# CCP_MCU.net
KiCad netlist of a schematic drawn in Altium Designer
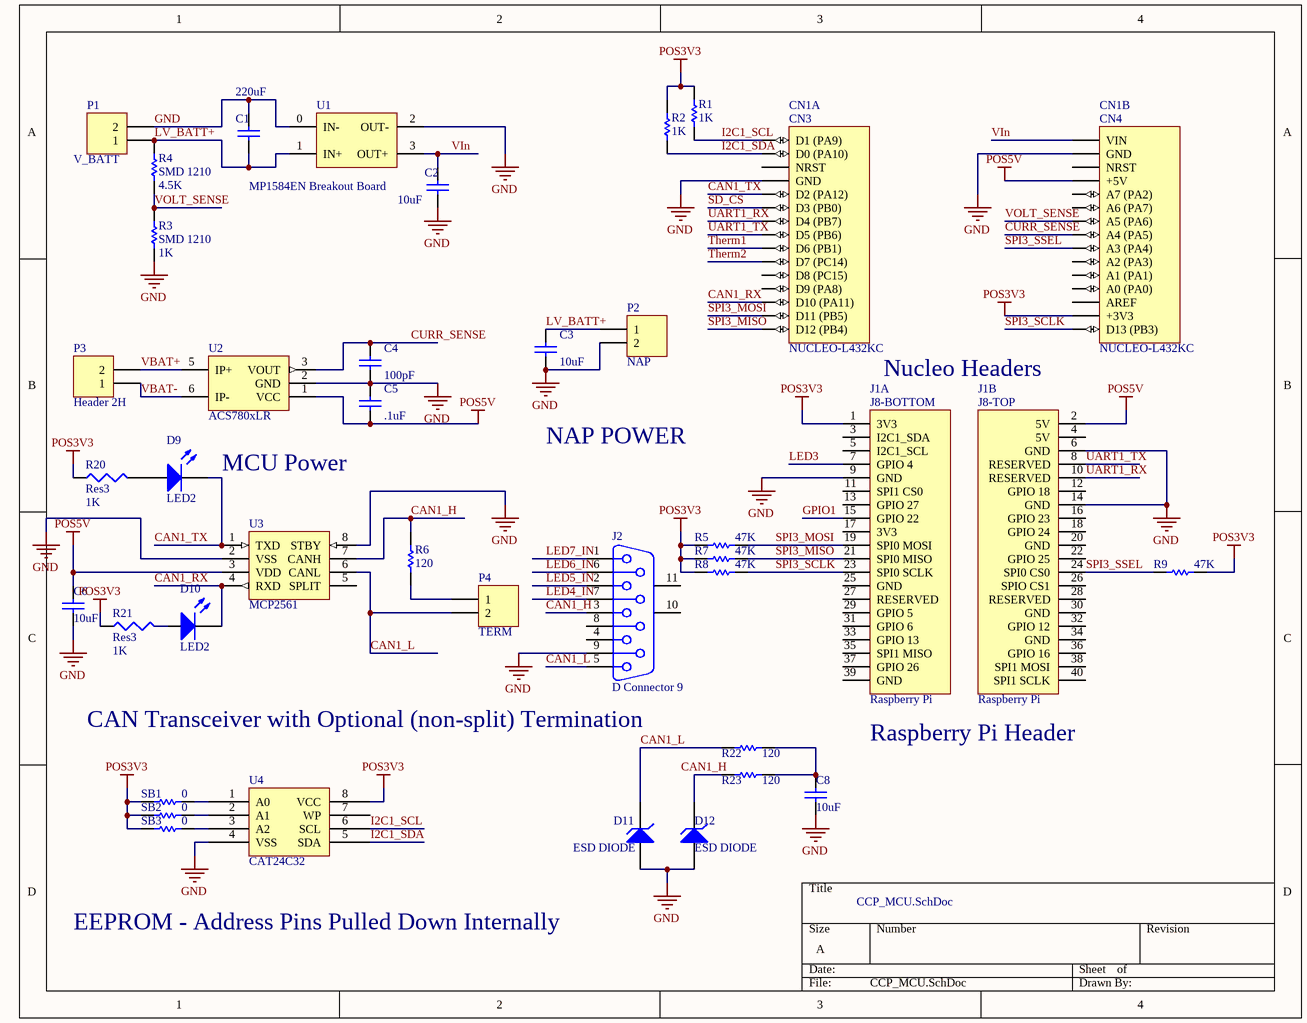
[diagram p0: CCP_MCU.SchDoc]

(export (version "E")
  (design (tool "Eeschema 10.0.6"))
  (components
    (comp (ref "C1")
      (value "220uF")
      (footprint "CAPR5-4X5")
      (description "Capacitor")
      (fields (field (name "Comment") "Cap") (field (name "PUBLISHER") "Altium Limited"))
      (libsource (lib "Miscellaneous Devices") (part "Cap"))
    )
    (comp (ref "C2")
      (value "10uF")
      (footprint "C1206")
      (description "Capacitor")
      (fields (field (name "Comment") "Cap") (field (name "PUBLISHER") "Altium Limited"))
      (libsource (lib "Miscellaneous Devices") (part "Cap"))
    )
    (comp (ref "C3")
      (value "10uF")
      (footprint "C1206")
      (description "Capacitor")
      (fields (field (name "Comment") "Cap") (field (name "PUBLISHER") "Altium Limited"))
      (libsource (lib "Miscellaneous Devices") (part "Cap"))
    )
    (comp (ref "C4")
      (value "100pF")
      (footprint "1608[0603]")
      (description "Capacitor (Semiconductor SIM Model)")
      (fields (field (name "Comment") "Cap Semi") (field (name "PUBLISHER") "Altium Limited"))
      (libsource (lib "Miscellaneous Devices") (part "Cap Semi"))
    )
    (comp (ref "C5")
      (value ".1uF")
      (footprint "C1206")
      (description "Capacitor (Semiconductor SIM Model)")
      (fields (field (name "Comment") "Cap Semi") (field (name "PUBLISHER") "Altium Limited"))
      (libsource (lib "Miscellaneous Devices") (part "Cap Semi"))
    )
    (comp (ref "C6")
      (value "10uF")
      (footprint "C1206")
      (description "Capacitor")
      (fields (field (name "Comment") "Cap") (field (name "PUBLISHER") "Altium Limited"))
      (libsource (lib "Miscellaneous Devices") (part "Cap"))
    )
    (comp (ref "C8")
      (value "10uF")
      (footprint "C1206")
      (description "Capacitor")
      (fields (field (name "Comment") "Cap") (field (name "PUBLISHER") "Altium Limited"))
      (libsource (lib "Miscellaneous Devices") (part "Cap"))
    )
    (comp (ref "CN1")
      (value "NUCLEO-L432KC")
      (footprint "NUCLEO-32")
      (description "STM32L432KC Development Board")
      (libsource (lib "ic") (part "NUCLEO-L432KC"))
    )
    (comp (ref "D9")
      (value "LED2")
      (footprint "3.2X1.6X1.1")
      (description "Typical RED, GREEN, YELLOW, AMBER GaAs LED")
      (fields (field (name "PUBLISHER") "Altium Limited"))
      (libsource (lib "Miscellaneous Devices") (part "LED2"))
    )
    (comp (ref "D10")
      (value "LED2")
      (footprint "3.2X1.6X1.1")
      (description "Typical RED, GREEN, YELLOW, AMBER GaAs LED")
      (fields (field (name "PUBLISHER") "Altium Limited"))
      (libsource (lib "Miscellaneous Devices") (part "LED2"))
    )
    (comp (ref "D11")
      (value "ESD DIODE")
      (footprint "6-0805_M")
      (description "Zener Diode")
      (fields (field (name "PUBLISHER") "Altium Limited"))
      (libsource (lib "Miscellaneous Devices") (part "D Zener"))
    )
    (comp (ref "D12")
      (value "ESD DIODE")
      (footprint "6-0805_M")
      (description "Zener Diode")
      (fields (field (name "PUBLISHER") "Altium Limited"))
      (libsource (lib "Miscellaneous Devices") (part "D Zener"))
    )
    (comp (ref "J1")
      (value "Raspberry Pi")
      (footprint "Raspberry Pi - CCP Outline")
      (description "2x20 Header")
      (libsource (lib "connector") (part "Raspberry Pi"))
    )
    (comp (ref "J2")
      (value "D Connector 9")
      (footprint "DSUB1.385-2H9")
      (description "Receptacle Assembly, 9 Position, Right Angle")
      (fields (field (name "PUBLISHER") "Altium Limited"))
      (libsource (lib "Miscellaneous Connectors") (part "D Connector 9"))
    )
    (comp (ref "P1")
      (value "V_BATT")
      (footprint "2POS TERM BLOCK")
      (description "Header, 2-Pin")
      (fields (field (name "PUBLISHER") "Altium Limited"))
      (libsource (lib "Miscellaneous Connectors") (part "Header 2"))
    )
    (comp (ref "P2")
      (value "NAP")
      (footprint "2POS TERM BLOCK")
      (description "Header, 2-Pin")
      (fields (field (name "PUBLISHER") "Altium Limited"))
      (libsource (lib "") (part "Header 2_1"))
    )
    (comp (ref "P3")
      (value "Header 2H")
      (footprint "2POS TERM BLOCK")
      (description "Header, 2-Pin, Right Angle")
      (fields (field (name "PUBLISHER") "Altium Limited"))
      (libsource (lib "Miscellaneous Connectors") (part "Header 2H"))
    )
    (comp (ref "P4")
      (value "TERM")
      (footprint "HDR1X2")
      (description "Header, 2-Pin")
      (fields (field (name "PUBLISHER") "Altium Limited"))
      (libsource (lib "") (part "Header 2_1"))
    )
    (comp (ref "R1")
      (value "1K")
      (footprint "6-0805_M")
      (description "Resistor")
      (fields (field (name "Comment") "Res1") (field (name "PUBLISHER") "Altium Limited"))
      (libsource (lib "Miscellaneous Devices") (part "Res1"))
    )
    (comp (ref "R2")
      (value "1K")
      (footprint "6-0805_M")
      (description "Resistor")
      (fields (field (name "Comment") "Res1") (field (name "PUBLISHER") "Altium Limited"))
      (libsource (lib "Miscellaneous Devices") (part "Res1"))
    )
    (comp (ref "R3")
      (value "SMD 1210")
      (footprint "14-1210")
      (description "Resistor")
      (fields (field (name "ALTIUM_VALUE") "1K") (field (name "PUBLISHER") "Altium Limited"))
      (libsource (lib "Miscellaneous Devices") (part "Res1"))
    )
    (comp (ref "R4")
      (value "SMD 1210")
      (footprint "14-1210")
      (description "Resistor")
      (fields (field (name "ALTIUM_VALUE") "4.5K") (field (name "PUBLISHER") "Altium Limited"))
      (libsource (lib "Miscellaneous Devices") (part "Res1"))
    )
    (comp (ref "R5")
      (value "47K")
      (footprint "6-0805_M")
      (description "Resistor")
      (fields (field (name "Comment") "Res1") (field (name "PUBLISHER") "Altium Limited"))
      (libsource (lib "Miscellaneous Devices") (part "Res1"))
    )
    (comp (ref "R6")
      (value "120")
      (footprint "6-0805_M")
      (description "Resistor")
      (fields (field (name "Comment") "Res1") (field (name "PUBLISHER") "Altium Limited"))
      (libsource (lib "Miscellaneous Devices") (part "Res1"))
    )
    (comp (ref "R7")
      (value "47K")
      (footprint "6-0805_M")
      (description "Resistor")
      (fields (field (name "Comment") "Res1") (field (name "PUBLISHER") "Altium Limited"))
      (libsource (lib "Miscellaneous Devices") (part "Res1"))
    )
    (comp (ref "R8")
      (value "47K")
      (footprint "6-0805_M")
      (description "Resistor")
      (fields (field (name "Comment") "Res1") (field (name "PUBLISHER") "Altium Limited"))
      (libsource (lib "Miscellaneous Devices") (part "Res1"))
    )
    (comp (ref "R9")
      (value "47K")
      (footprint "6-0805_M")
      (description "Resistor")
      (fields (field (name "Comment") "Res1") (field (name "PUBLISHER") "Altium Limited"))
      (libsource (lib "Miscellaneous Devices") (part "Res1"))
    )
    (comp (ref "R20")
      (value "Res3")
      (footprint "J1-0603")
      (description "Resistor")
      (fields (field (name "ALTIUM_VALUE") "1K") (field (name "PUBLISHER") "Altium Limited"))
      (libsource (lib "Miscellaneous Devices") (part "Res3"))
    )
    (comp (ref "R21")
      (value "Res3")
      (footprint "J1-0603")
      (description "Resistor")
      (fields (field (name "ALTIUM_VALUE") "1K") (field (name "PUBLISHER") "Altium Limited"))
      (libsource (lib "Miscellaneous Devices") (part "Res3"))
    )
    (comp (ref "R22")
      (value "120")
      (footprint "6-0805_M")
      (description "Resistor")
      (fields (field (name "Comment") "Res1") (field (name "PUBLISHER") "Altium Limited"))
      (libsource (lib "Miscellaneous Devices") (part "Res1"))
    )
    (comp (ref "R23")
      (value "120")
      (footprint "6-0805_M")
      (description "Resistor")
      (fields (field (name "Comment") "Res1") (field (name "PUBLISHER") "Altium Limited"))
      (libsource (lib "Miscellaneous Devices") (part "Res1"))
    )
    (comp (ref "SB1")
      (value "0")
      (footprint "6-0805_M")
      (description "Resistor")
      (fields (field (name "Comment") "Res1") (field (name "PUBLISHER") "Altium Limited"))
      (libsource (lib "Miscellaneous Devices") (part "Res1"))
    )
    (comp (ref "SB2")
      (value "0")
      (footprint "6-0805_M")
      (description "Resistor")
      (fields (field (name "Comment") "Res1") (field (name "PUBLISHER") "Altium Limited"))
      (libsource (lib "Miscellaneous Devices") (part "Res1"))
    )
    (comp (ref "SB3")
      (value "0")
      (footprint "6-0805_M")
      (description "Resistor")
      (fields (field (name "Comment") "Res1") (field (name "PUBLISHER") "Altium Limited"))
      (libsource (lib "Miscellaneous Devices") (part "Res1"))
    )
    (comp (ref "U1")
      (value "MP1584EN Breakout Board")
      (footprint "MP1584EN Breakout")
      (description "Buck Converter")
      (libsource (lib "ic") (part "MP1584EN Breakout Board"))
    )
    (comp (ref "U2")
      (value "ACS780xLR")
      (footprint "7-pin PSOF")
      (description "Hall-Effect Current Sensor")
      (libsource (lib "ic") (part "ACS780xLR"))
    )
    (comp (ref "U3")
      (value "MCP2561")
      (footprint "SO8_L")
      (description "CAN Transciever")
      (libsource (lib "ic") (part "MCP2561"))
    )
    (comp (ref "U4")
      (value "CAT24C32")
      (footprint "SO8_N")
      (description "I2C EEPROM")
      (libsource (lib "ic") (part "CAT24C32"))
    )
  )
  (nets
    (net (code "1") (name "/CAN1_H") (class "Default")
      (node (ref "J2") (pin "3") (pinfunction "3_3") (pintype "passive"))
      (node (ref "R6") (pin "2") (pinfunction "2_2") (pintype "passive"))
      (node (ref "U3") (pin "7") (pinfunction "CANH_7") (pintype "passive"))
    )
    (net (code "2") (name "/CAN1_L") (class "Default")
      (node (ref "D11") (pin "2") (pinfunction "K_2") (pintype "passive"))
      (node (ref "J2") (pin "5") (pinfunction "5_5") (pintype "passive"))
      (node (ref "P4") (pin "2") (pinfunction "2_2") (pintype "passive"))
      (node (ref "R22") (pin "2") (pinfunction "2_2") (pintype "passive"))
      (node (ref "U3") (pin "6") (pinfunction "CANL_6") (pintype "passive"))
    )
    (net (code "3") (name "/CAN1_RX") (class "Default")
      (node (ref "CN1") (pin "13") (pinfunction "D10_(PA11)_13") (pintype "bidirectional"))
      (node (ref "D10") (pin "2") (pinfunction "K_2") (pintype "passive"))
      (node (ref "U3") (pin "4") (pinfunction "RXD_4") (pintype "output"))
    )
    (net (code "4") (name "/CAN1_TX") (class "Default")
      (node (ref "CN1") (pin "5") (pinfunction "D2_(PA12)_5") (pintype "bidirectional"))
      (node (ref "D9") (pin "2") (pinfunction "K_2") (pintype "passive"))
      (node (ref "U3") (pin "1") (pinfunction "TXD_1") (pintype "input"))
    )
    (net (code "5") (name "/CURR_SENSE") (class "Default")
      (node (ref "C4") (pin "2") (pinfunction "2_2") (pintype "passive"))
      (node (ref "CN1") (pin "23") (pinfunction "A4_(PA5)_23") (pintype "bidirectional"))
      (node (ref "U2") (pin "3") (pinfunction "VOUT_3") (pintype "output"))
    )
    (net (code "6") (name "/GPIO1") (class "Default")
      (node (ref "J1") (pin "15") (pinfunction "GPIO_22_15") (pintype "passive"))
    )
    (net (code "7") (name "/I2C1_SCL") (class "Default")
      (node (ref "CN1") (pin "1") (pinfunction "D1_(PA9)_1") (pintype "bidirectional"))
      (node (ref "R1") (pin "1") (pinfunction "1_1") (pintype "passive"))
      (node (ref "U4") (pin "6") (pinfunction "SCL_6") (pintype "passive"))
    )
    (net (code "8") (name "/I2C1_SDA") (class "Default")
      (node (ref "CN1") (pin "2") (pinfunction "D0_(PA10)_2") (pintype "bidirectional"))
      (node (ref "R2") (pin "1") (pinfunction "1_1") (pintype "passive"))
      (node (ref "U4") (pin "5") (pinfunction "SDA_5") (pintype "passive"))
    )
    (net (code "9") (name "/LED3") (class "Default")
      (node (ref "J1") (pin "7") (pinfunction "GPIO_4_7") (pintype "passive"))
    )
    (net (code "10") (name "/LED4_IN") (class "Default")
      (node (ref "J2") (pin "7") (pinfunction "7_7") (pintype "passive"))
    )
    (net (code "11") (name "/LED5_IN") (class "Default")
      (node (ref "J2") (pin "2") (pinfunction "2_2") (pintype "passive"))
    )
    (net (code "12") (name "/LED6_IN") (class "Default")
      (node (ref "J2") (pin "6") (pinfunction "6_6") (pintype "passive"))
    )
    (net (code "13") (name "/LED7_IN") (class "Default")
      (node (ref "J2") (pin "1") (pinfunction "1_1") (pintype "passive"))
    )
    (net (code "14") (name "/LV_BATT+") (class "Default")
      (node (ref "C1") (pin "1") (pinfunction "1_1") (pintype "passive"))
      (node (ref "C3") (pin "2") (pinfunction "2_2") (pintype "passive"))
      (node (ref "P1") (pin "1") (pinfunction "1_1") (pintype "passive"))
      (node (ref "P2") (pin "1") (pinfunction "1_1") (pintype "passive"))
      (node (ref "R4") (pin "1") (pinfunction "1_1") (pintype "passive"))
      (node (ref "U1") (pin "1") (pinfunction "IN+_1") (pintype "power_in"))
    )
    (net (code "15") (name "/SD_CS") (class "Default")
      (node (ref "CN1") (pin "6") (pinfunction "D3_(PB0)_6") (pintype "bidirectional"))
    )
    (net (code "16") (name "/SPI3_MISO") (class "Default")
      (node (ref "CN1") (pin "15") (pinfunction "D12_(PB4)_15") (pintype "bidirectional"))
      (node (ref "J1") (pin "21") (pinfunction "SPI0_MISO_21") (pintype "passive"))
      (node (ref "R7") (pin "2") (pinfunction "2_2") (pintype "passive"))
    )
    (net (code "17") (name "/SPI3_MOSI") (class "Default")
      (node (ref "CN1") (pin "14") (pinfunction "D11_(PB5)_14") (pintype "bidirectional"))
      (node (ref "J1") (pin "19") (pinfunction "SPI0_MOSI_19") (pintype "passive"))
      (node (ref "R5") (pin "2") (pinfunction "2_2") (pintype "passive"))
    )
    (net (code "18") (name "/SPI3_SCLK") (class "Default")
      (node (ref "CN1") (pin "16") (pinfunction "D13_(PB3)_16") (pintype "bidirectional"))
      (node (ref "J1") (pin "23") (pinfunction "SPI0_SCLK_23") (pintype "passive"))
      (node (ref "R8") (pin "2") (pinfunction "2_2") (pintype "passive"))
    )
    (net (code "19") (name "/SPI3_SSEL") (class "Default")
      (node (ref "CN1") (pin "22") (pinfunction "A3_(PA4)_22") (pintype "bidirectional"))
      (node (ref "J1") (pin "24") (pinfunction "SPI0_CS0_24") (pintype "passive"))
      (node (ref "R9") (pin "1") (pinfunction "1_1") (pintype "passive"))
    )
    (net (code "20") (name "/Therm1") (class "Default")
      (node (ref "CN1") (pin "9") (pinfunction "D6_(PB1)_9") (pintype "bidirectional"))
    )
    (net (code "21") (name "/Therm2") (class "Default")
      (node (ref "CN1") (pin "10") (pinfunction "D7_(PC14)_10") (pintype "bidirectional"))
    )
    (net (code "22") (name "/UART1_RX") (class "Default")
      (node (ref "CN1") (pin "7") (pinfunction "D4_(PB7)_7") (pintype "bidirectional"))
      (node (ref "J1") (pin "10") (pinfunction "RESERVED_10") (pintype "passive"))
    )
    (net (code "23") (name "/UART1_TX") (class "Default")
      (node (ref "CN1") (pin "8") (pinfunction "D5_(PB6)_8") (pintype "bidirectional"))
      (node (ref "J1") (pin "8") (pinfunction "RESERVED_8") (pintype "passive"))
    )
    (net (code "24") (name "/VBAT+") (class "Default")
      (node (ref "P3") (pin "2") (pinfunction "2_2") (pintype "passive"))
      (node (ref "U2") (pin "5") (pinfunction "IP+_5") (pintype "passive"))
    )
    (net (code "25") (name "/VBAT-") (class "Default")
      (node (ref "P3") (pin "1") (pinfunction "1_1") (pintype "passive"))
      (node (ref "U2") (pin "6") (pinfunction "IP-_6") (pintype "passive"))
    )
    (net (code "26") (name "/VIn") (class "Default")
      (node (ref "C2") (pin "2") (pinfunction "2_2") (pintype "passive"))
      (node (ref "CN1") (pin "30") (pinfunction "VIN_30") (pintype "power_in"))
      (node (ref "U1") (pin "3") (pinfunction "OUT+_3") (pintype "power_in"))
    )
    (net (code "27") (name "/VOLT_SENSE") (class "Default")
      (node (ref "CN1") (pin "24") (pinfunction "A5_(PA6)_24") (pintype "bidirectional"))
      (node (ref "R3") (pin "1") (pinfunction "1_1") (pintype "passive"))
      (node (ref "R4") (pin "2") (pinfunction "2_2") (pintype "passive"))
    )
    (net (code "28") (name "GND") (class "Default")
      (node (ref "C1") (pin "2") (pinfunction "2_2") (pintype "passive"))
      (node (ref "C2") (pin "1") (pinfunction "1_1") (pintype "passive"))
      (node (ref "C3") (pin "1") (pinfunction "1_1") (pintype "passive"))
      (node (ref "C4") (pin "1") (pinfunction "1_1") (pintype "passive"))
      (node (ref "C5") (pin "2") (pinfunction "2_2") (pintype "passive"))
      (node (ref "C6") (pin "1") (pinfunction "1_1") (pintype "passive"))
      (node (ref "C8") (pin "1") (pinfunction "1_1") (pintype "passive"))
      (node (ref "CN1") (pin "29") (pinfunction "GND_29") (pintype "power_in"))
      (node (ref "CN1") (pin "4") (pinfunction "GND_4") (pintype "power_in"))
      (node (ref "D11") (pin "1") (pinfunction "A_1") (pintype "passive"))
      (node (ref "D12") (pin "1") (pinfunction "A_1") (pintype "passive"))
      (node (ref "J1") (pin "14") (pinfunction "GND_14") (pintype "passive"))
      (node (ref "J1") (pin "6") (pinfunction "GND_6") (pintype "passive"))
      (node (ref "J1") (pin "9") (pinfunction "GND_9") (pintype "passive"))
      (node (ref "J2") (pin "9") (pinfunction "9_9") (pintype "passive"))
      (node (ref "P1") (pin "2") (pinfunction "2_2") (pintype "passive"))
      (node (ref "P2") (pin "2") (pinfunction "2_2") (pintype "passive"))
      (node (ref "R3") (pin "2") (pinfunction "2_2") (pintype "passive"))
      (node (ref "U1") (pin "0") (pinfunction "IN-_0") (pintype "power_in"))
      (node (ref "U1") (pin "2") (pinfunction "OUT-_2") (pintype "power_in"))
      (node (ref "U2") (pin "2") (pinfunction "GND_2") (pintype "power_in"))
      (node (ref "U3") (pin "2") (pinfunction "VSS_2") (pintype "power_in"))
      (node (ref "U3") (pin "8") (pinfunction "STBY_8") (pintype "input"))
      (node (ref "U4") (pin "4") (pinfunction "VSS_4") (pintype "passive"))
    )
    (net (code "29") (name "Net-(C8-Pad2)") (class "Default")
      (node (ref "C8") (pin "2") (pinfunction "2_2") (pintype "passive"))
      (node (ref "R22") (pin "1") (pinfunction "1_1") (pintype "passive"))
      (node (ref "R23") (pin "1") (pinfunction "1_1") (pintype "passive"))
    )
    (net (code "30") (name "Net-(D9-A)") (class "Default")
      (node (ref "D9") (pin "1") (pinfunction "A_1") (pintype "passive"))
      (node (ref "R20") (pin "2") (pinfunction "2_2") (pintype "passive"))
    )
    (net (code "31") (name "Net-(D10-A)") (class "Default")
      (node (ref "D10") (pin "1") (pinfunction "A_1") (pintype "passive"))
      (node (ref "R21") (pin "2") (pinfunction "2_2") (pintype "passive"))
    )
    (net (code "32") (name "Net-(D12-K)") (class "Default")
      (node (ref "D12") (pin "2") (pinfunction "K_2") (pintype "passive"))
      (node (ref "R23") (pin "2") (pinfunction "2_2") (pintype "passive"))
    )
    (net (code "33") (name "Net-(P4-Pad1)") (class "Default")
      (node (ref "P4") (pin "1") (pinfunction "1_1") (pintype "passive"))
      (node (ref "R6") (pin "1") (pinfunction "1_1") (pintype "passive"))
    )
    (net (code "34") (name "Net-(U4-A0)") (class "Default")
      (node (ref "SB1") (pin "1") (pinfunction "1_1") (pintype "passive"))
      (node (ref "U4") (pin "1") (pinfunction "A0_1") (pintype "passive"))
    )
    (net (code "35") (name "Net-(U4-A1)") (class "Default")
      (node (ref "SB2") (pin "1") (pinfunction "1_1") (pintype "passive"))
      (node (ref "U4") (pin "2") (pinfunction "A1_2") (pintype "passive"))
    )
    (net (code "36") (name "Net-(U4-A2)") (class "Default")
      (node (ref "SB3") (pin "1") (pinfunction "1_1") (pintype "passive"))
      (node (ref "U4") (pin "3") (pinfunction "A2_3") (pintype "passive"))
    )
    (net (code "37") (name "POS3V3") (class "Default")
      (node (ref "CN1") (pin "17") (pinfunction "+3V3_17") (pintype "power_in"))
      (node (ref "J1") (pin "1") (pinfunction "3V3_1") (pintype "passive"))
      (node (ref "R1") (pin "2") (pinfunction "2_2") (pintype "passive"))
      (node (ref "R2") (pin "2") (pinfunction "2_2") (pintype "passive"))
      (node (ref "R20") (pin "1") (pinfunction "1_1") (pintype "passive"))
      (node (ref "R21") (pin "1") (pinfunction "1_1") (pintype "passive"))
      (node (ref "R5") (pin "1") (pinfunction "1_1") (pintype "passive"))
      (node (ref "R7") (pin "1") (pinfunction "1_1") (pintype "passive"))
      (node (ref "R8") (pin "1") (pinfunction "1_1") (pintype "passive"))
      (node (ref "R9") (pin "2") (pinfunction "2_2") (pintype "passive"))
      (node (ref "SB1") (pin "2") (pinfunction "2_2") (pintype "passive"))
      (node (ref "SB2") (pin "2") (pinfunction "2_2") (pintype "passive"))
      (node (ref "SB3") (pin "2") (pinfunction "2_2") (pintype "passive"))
      (node (ref "U4") (pin "8") (pinfunction "VCC_8") (pintype "power_in"))
    )
    (net (code "38") (name "POS5V") (class "Default")
      (node (ref "C5") (pin "1") (pinfunction "1_1") (pintype "passive"))
      (node (ref "C6") (pin "2") (pinfunction "2_2") (pintype "passive"))
      (node (ref "CN1") (pin "27") (pinfunction "+5V_27") (pintype "power_in"))
      (node (ref "J1") (pin "2") (pinfunction "5V_2") (pintype "passive"))
      (node (ref "U2") (pin "1") (pinfunction "VCC_1") (pintype "power_in"))
      (node (ref "U3") (pin "3") (pinfunction "VDD_3") (pintype "passive"))
    )
    (net (code "39") (name "unconnected-(CN1A-D8_(PC15)-Pad11)") (class "Default")
      (node (ref "CN1") (pin "11") (pinfunction "D8_(PC15)_11") (pintype "bidirectional"))
    )
    (net (code "40") (name "unconnected-(CN1A-D9_(PA8)-Pad12)") (class "Default")
      (node (ref "CN1") (pin "12") (pinfunction "D9_(PA8)_12") (pintype "bidirectional"))
    )
    (net (code "41") (name "unconnected-(CN1A-NRST-Pad3)") (class "Default")
      (node (ref "CN1") (pin "3") (pinfunction "NRST_3") (pintype "passive"))
    )
    (net (code "42") (name "unconnected-(CN1B-A0_(PA0)-Pad19)") (class "Default")
      (node (ref "CN1") (pin "19") (pinfunction "A0_(PA0)_19") (pintype "bidirectional"))
    )
    (net (code "43") (name "unconnected-(CN1B-A1_(PA1)-Pad20)") (class "Default")
      (node (ref "CN1") (pin "20") (pinfunction "A1_(PA1)_20") (pintype "bidirectional"))
    )
    (net (code "44") (name "unconnected-(CN1B-A2_(PA3)-Pad21)") (class "Default")
      (node (ref "CN1") (pin "21") (pinfunction "A2_(PA3)_21") (pintype "bidirectional"))
    )
    (net (code "45") (name "unconnected-(CN1B-A6_(PA7)-Pad25)") (class "Default")
      (node (ref "CN1") (pin "25") (pinfunction "A6_(PA7)_25") (pintype "bidirectional"))
    )
    (net (code "46") (name "unconnected-(CN1B-A7_(PA2)-Pad26)") (class "Default")
      (node (ref "CN1") (pin "26") (pinfunction "A7_(PA2)_26") (pintype "bidirectional"))
    )
    (net (code "47") (name "unconnected-(CN1B-AREF-Pad18)") (class "Default")
      (node (ref "CN1") (pin "18") (pinfunction "AREF_18") (pintype "passive"))
    )
    (net (code "48") (name "unconnected-(CN1B-NRST-Pad28)") (class "Default")
      (node (ref "CN1") (pin "28") (pinfunction "NRST_28") (pintype "passive"))
    )
    (net (code "49") (name "unconnected-(J1A-3V3-Pad17)") (class "Default")
      (node (ref "J1") (pin "17") (pinfunction "3V3_17") (pintype "passive"))
    )
    (net (code "50") (name "unconnected-(J1A-GND-Pad25)") (class "Default")
      (node (ref "J1") (pin "25") (pinfunction "GND_25") (pintype "passive"))
    )
    (net (code "51") (name "unconnected-(J1A-GND-Pad39)") (class "Default")
      (node (ref "J1") (pin "39") (pinfunction "GND_39") (pintype "passive"))
    )
    (net (code "52") (name "unconnected-(J1A-GPIO_5-Pad29)") (class "Default")
      (node (ref "J1") (pin "29") (pinfunction "GPIO_5_29") (pintype "passive"))
    )
    (net (code "53") (name "unconnected-(J1A-GPIO_6-Pad31)") (class "Default")
      (node (ref "J1") (pin "31") (pinfunction "GPIO_6_31") (pintype "passive"))
    )
    (net (code "54") (name "unconnected-(J1A-GPIO_13-Pad33)") (class "Default")
      (node (ref "J1") (pin "33") (pinfunction "GPIO_13_33") (pintype "passive"))
    )
    (net (code "55") (name "unconnected-(J1A-GPIO_26-Pad37)") (class "Default")
      (node (ref "J1") (pin "37") (pinfunction "GPIO_26_37") (pintype "passive"))
    )
    (net (code "56") (name "unconnected-(J1A-GPIO_27-Pad13)") (class "Default")
      (node (ref "J1") (pin "13") (pinfunction "GPIO_27_13") (pintype "passive"))
    )
    (net (code "57") (name "unconnected-(J1A-I2C1_SCL-Pad5)") (class "Default")
      (node (ref "J1") (pin "5") (pinfunction "I2C1_SCL_5") (pintype "passive"))
    )
    (net (code "58") (name "unconnected-(J1A-I2C1_SDA-Pad3)") (class "Default")
      (node (ref "J1") (pin "3") (pinfunction "I2C1_SDA_3") (pintype "passive"))
    )
    (net (code "59") (name "unconnected-(J1A-RESERVED-Pad27)") (class "Default")
      (node (ref "J1") (pin "27") (pinfunction "RESERVED_27") (pintype "passive"))
    )
    (net (code "60") (name "unconnected-(J1A-SPI1_CS0-Pad11)") (class "Default")
      (node (ref "J1") (pin "11") (pinfunction "SPI1_CS0_11") (pintype "passive"))
    )
    (net (code "61") (name "unconnected-(J1A-SPI1_MISO-Pad35)") (class "Default")
      (node (ref "J1") (pin "35") (pinfunction "SPI1_MISO_35") (pintype "passive"))
    )
    (net (code "62") (name "unconnected-(J1B-5V-Pad4)") (class "Default")
      (node (ref "J1") (pin "4") (pinfunction "5V_4") (pintype "passive"))
    )
    (net (code "63") (name "unconnected-(J1B-GND-Pad20)") (class "Default")
      (node (ref "J1") (pin "20") (pinfunction "GND_20") (pintype "passive"))
    )
    (net (code "64") (name "unconnected-(J1B-GND-Pad30)") (class "Default")
      (node (ref "J1") (pin "30") (pinfunction "GND_30") (pintype "passive"))
    )
    (net (code "65") (name "unconnected-(J1B-GND-Pad34)") (class "Default")
      (node (ref "J1") (pin "34") (pinfunction "GND_34") (pintype "passive"))
    )
    (net (code "66") (name "unconnected-(J1B-GPIO_12-Pad32)") (class "Default")
      (node (ref "J1") (pin "32") (pinfunction "GPIO_12_32") (pintype "passive"))
    )
    (net (code "67") (name "unconnected-(J1B-GPIO_16-Pad36)") (class "Default")
      (node (ref "J1") (pin "36") (pinfunction "GPIO_16_36") (pintype "passive"))
    )
    (net (code "68") (name "unconnected-(J1B-GPIO_18-Pad12)") (class "Default")
      (node (ref "J1") (pin "12") (pinfunction "GPIO_18_12") (pintype "passive"))
    )
    (net (code "69") (name "unconnected-(J1B-GPIO_23-Pad16)") (class "Default")
      (node (ref "J1") (pin "16") (pinfunction "GPIO_23_16") (pintype "passive"))
    )
    (net (code "70") (name "unconnected-(J1B-GPIO_24-Pad18)") (class "Default")
      (node (ref "J1") (pin "18") (pinfunction "GPIO_24_18") (pintype "passive"))
    )
    (net (code "71") (name "unconnected-(J1B-GPIO_25-Pad22)") (class "Default")
      (node (ref "J1") (pin "22") (pinfunction "GPIO_25_22") (pintype "passive"))
    )
    (net (code "72") (name "unconnected-(J1B-RESERVED-Pad28)") (class "Default")
      (node (ref "J1") (pin "28") (pinfunction "RESERVED_28") (pintype "passive"))
    )
    (net (code "73") (name "unconnected-(J1B-SPI1_MOSI-Pad38)") (class "Default")
      (node (ref "J1") (pin "38") (pinfunction "SPI1_MOSI_38") (pintype "passive"))
    )
    (net (code "74") (name "unconnected-(J1B-SPI1_SCLK-Pad40)") (class "Default")
      (node (ref "J1") (pin "40") (pinfunction "SPI1_SCLK_40") (pintype "passive"))
    )
    (net (code "75") (name "unconnected-(J1B-SPIO_CS1-Pad26)") (class "Default")
      (node (ref "J1") (pin "26") (pinfunction "SPIO_CS1_26") (pintype "passive"))
    )
    (net (code "76") (name "unconnected-(J2-MH1-Pad10)") (class "Default")
      (node (ref "J2") (pin "10") (pinfunction "MH1_10") (pintype "passive"))
    )
    (net (code "77") (name "unconnected-(J2-MH2-Pad11)") (class "Default")
      (node (ref "J2") (pin "11") (pinfunction "MH2_11") (pintype "passive"))
    )
    (net (code "78") (name "unconnected-(J2-Pad4)") (class "Default")
      (node (ref "J2") (pin "4") (pinfunction "4_4") (pintype "passive"))
    )
    (net (code "79") (name "unconnected-(J2-Pad8)") (class "Default")
      (node (ref "J2") (pin "8") (pinfunction "8_8") (pintype "passive"))
    )
    (net (code "80") (name "unconnected-(U3-SPLIT-Pad5)") (class "Default")
      (node (ref "U3") (pin "5") (pinfunction "SPLIT_5") (pintype "passive"))
    )
    (net (code "81") (name "unconnected-(U4-WP-Pad7)") (class "Default")
      (node (ref "U4") (pin "7") (pinfunction "WP_7") (pintype "passive"))
    )
  )
)
